# SD.net
KiCad netlist of a schematic drawn in Altium Designer
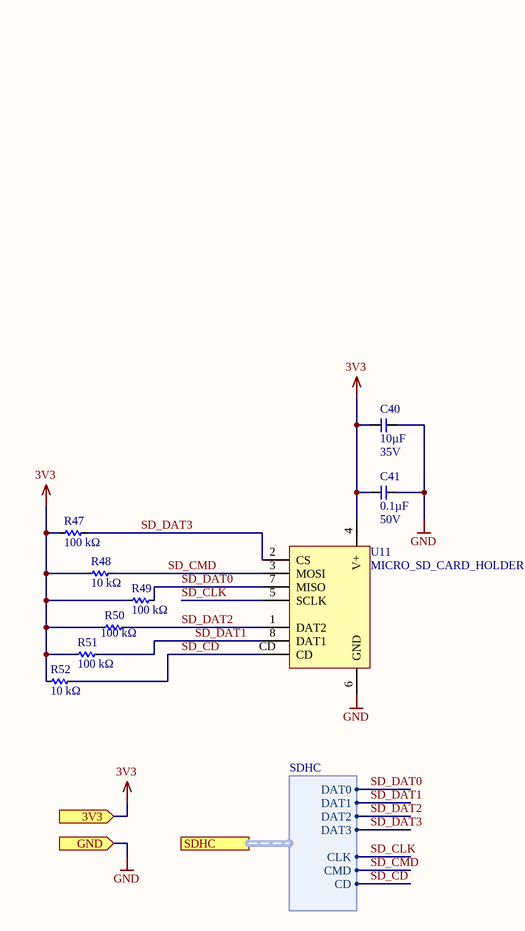
[diagram p0: SD.SchDoc]

(export (version "E")
  (design (tool "Eeschema 10.0.6"))
  (components
    (comp (ref "C40")
      (value "490-13248-1-ND")
      (footprint "C0603")
      (description "CAP CER 10UF 35V X5R 0603 20%")
      (fields
        (field (name "CAPACITANCE (SHORTHAND)") "10µF")
        (field (name "RATED VOLTAGE") "35V")
        (field (name "MANUFACTURER") "Murata Electronics North America")
      )
      (libsource (lib "Stanford Student Space Initiative") (part "__template_cap"))
    )
    (comp (ref "C41")
      (value "490-1519-1-ND")
      (footprint "C0603")
      (description "CAP CER 0603 0.1µF X7R 50V 10%")
      (fields
        (field (name "CAPACITANCE (SHORTHAND)") "0.1µF")
        (field (name "RATED VOLTAGE") "50V")
        (field (name "MANUFACTURER") "Murata Electronics North America")
      )
      (libsource (lib "Stanford Student Space Initiative") (part "__template_cap"))
    )
    (comp (ref "R47")
      (value "311-100KHRCT-ND")
      (footprint "R0603")
      (description "RES SMD 100K OHM 1% 1/10W 0603")
      (fields
        (field (name "RESISTANCE") "100 kΩ")
        (field (name "MANUFACTURER PART NUMBER") "RC0603FR-07100KL")
        (field (name "MANUFACTURER") "Yageo")
      )
      (libsource (lib "Stanford Student Space Initiative") (part "__template_resistor"))
    )
    (comp (ref "R48")
      (value "311-10.0KHRCT-ND")
      (footprint "R0603")
      (description "RES SMD 10K OHM 1% 1/10W 0603")
      (fields
        (field (name "RESISTANCE") "10 kΩ")
        (field (name "MANUFACTURER PART NUMBER") "RC0603FR-0710KL")
        (field (name "MANUFACTURER") "Yageo")
      )
      (libsource (lib "Stanford Student Space Initiative") (part "__template_resistor"))
    )
    (comp (ref "R49")
      (value "311-100KHRCT-ND")
      (footprint "R0603")
      (description "RES SMD 100K OHM 1% 1/10W 0603")
      (fields
        (field (name "RESISTANCE") "100 kΩ")
        (field (name "MANUFACTURER PART NUMBER") "RC0603FR-07100KL")
        (field (name "MANUFACTURER") "Yageo")
      )
      (libsource (lib "Stanford Student Space Initiative") (part "__template_resistor"))
    )
    (comp (ref "R50")
      (value "311-100KHRCT-ND")
      (footprint "R0603")
      (description "RES SMD 100K OHM 1% 1/10W 0603")
      (fields
        (field (name "RESISTANCE") "100 kΩ")
        (field (name "MANUFACTURER PART NUMBER") "RC0603FR-07100KL")
        (field (name "MANUFACTURER") "Yageo")
      )
      (libsource (lib "Stanford Student Space Initiative") (part "__template_resistor"))
    )
    (comp (ref "R51")
      (value "311-100KHRCT-ND")
      (footprint "R0603")
      (description "RES SMD 100K OHM 1% 1/10W 0603")
      (fields
        (field (name "RESISTANCE") "100 kΩ")
        (field (name "MANUFACTURER PART NUMBER") "RC0603FR-07100KL")
        (field (name "MANUFACTURER") "Yageo")
      )
      (libsource (lib "Stanford Student Space Initiative") (part "__template_resistor"))
    )
    (comp (ref "R52")
      (value "311-10.0KHRCT-ND")
      (footprint "R0603")
      (description "RES SMD 10K OHM 1% 1/10W 0603")
      (fields
        (field (name "RESISTANCE") "10 kΩ")
        (field (name "MANUFACTURER PART NUMBER") "RC0603FR-0710KL")
        (field (name "MANUFACTURER") "Yageo")
      )
      (libsource (lib "Stanford Student Space Initiative") (part "__template_resistor"))
    )
    (comp (ref "U11")
      (value "MICRO_SD_CARD_HOLDER")
      (footprint "MICROSD_CARD_SOCKET")
      (description "MICROSD CARD HOLDER, PUSH-PUSH")
      (fields (field (name "MANUFACTURER") "3M") (field (name "MANUFACTURER PART NUMBER") "2908-05WB-MG"))
      (libsource (lib "Stanford Student Space Initiative") (part "MICRO_SD_CARD_HOLDER"))
    )
  )
  (nets
    (net (code "2") (name "/SD_CD") (class "Default")
      (node (ref "R52") (pin "2") (pintype "passive"))
      (node (ref "U11") (pin "CD") (pinfunction "CD_CD") (pintype "passive"))
    )
    (net (code "3") (name "/SD_CLK") (class "Default")
      (node (ref "U11") (pin "5") (pinfunction "SCLK_5") (pintype "passive"))
    )
    (net (code "4") (name "/SD_CMD") (class "Default")
      (node (ref "R48") (pin "2") (pintype "passive"))
      (node (ref "U11") (pin "3") (pinfunction "MOSI_3") (pintype "passive"))
    )
    (net (code "5") (name "/SD_DAT0") (class "Default")
      (node (ref "R49") (pin "2") (pintype "passive"))
      (node (ref "U11") (pin "7") (pinfunction "MISO_7") (pintype "passive"))
    )
    (net (code "6") (name "/SD_DAT1") (class "Default")
      (node (ref "R51") (pin "2") (pintype "passive"))
      (node (ref "U11") (pin "8") (pinfunction "DAT1_8") (pintype "passive"))
    )
    (net (code "7") (name "/SD_DAT2") (class "Default")
      (node (ref "R50") (pin "2") (pintype "passive"))
      (node (ref "U11") (pin "1") (pinfunction "DAT2_1") (pintype "passive"))
    )
    (net (code "8") (name "/SD_DAT3") (class "Default")
      (node (ref "R47") (pin "2") (pintype "passive"))
      (node (ref "U11") (pin "2") (pinfunction "CS_2") (pintype "passive"))
    )
    (net (code "10") (name "3V3") (class "Default")
      (node (ref "C40") (pin "2") (pintype "passive"))
      (node (ref "C41") (pin "1") (pintype "passive"))
      (node (ref "R47") (pin "1") (pintype "passive"))
      (node (ref "R48") (pin "1") (pintype "passive"))
      (node (ref "R49") (pin "1") (pintype "passive"))
      (node (ref "R50") (pin "1") (pintype "passive"))
      (node (ref "R51") (pin "1") (pintype "passive"))
      (node (ref "R52") (pin "1") (pintype "passive"))
      (node (ref "U11") (pin "4") (pinfunction "V+_4") (pintype "passive"))
    )
    (net (code "11") (name "GND") (class "Default")
      (node (ref "C40") (pin "1") (pintype "passive"))
      (node (ref "C41") (pin "2") (pintype "passive"))
      (node (ref "U11") (pin "6") (pinfunction "GND_6") (pintype "passive"))
    )
  )
)
